# nanoRF.net
KiCad netlist of a schematic drawn in EAGLE
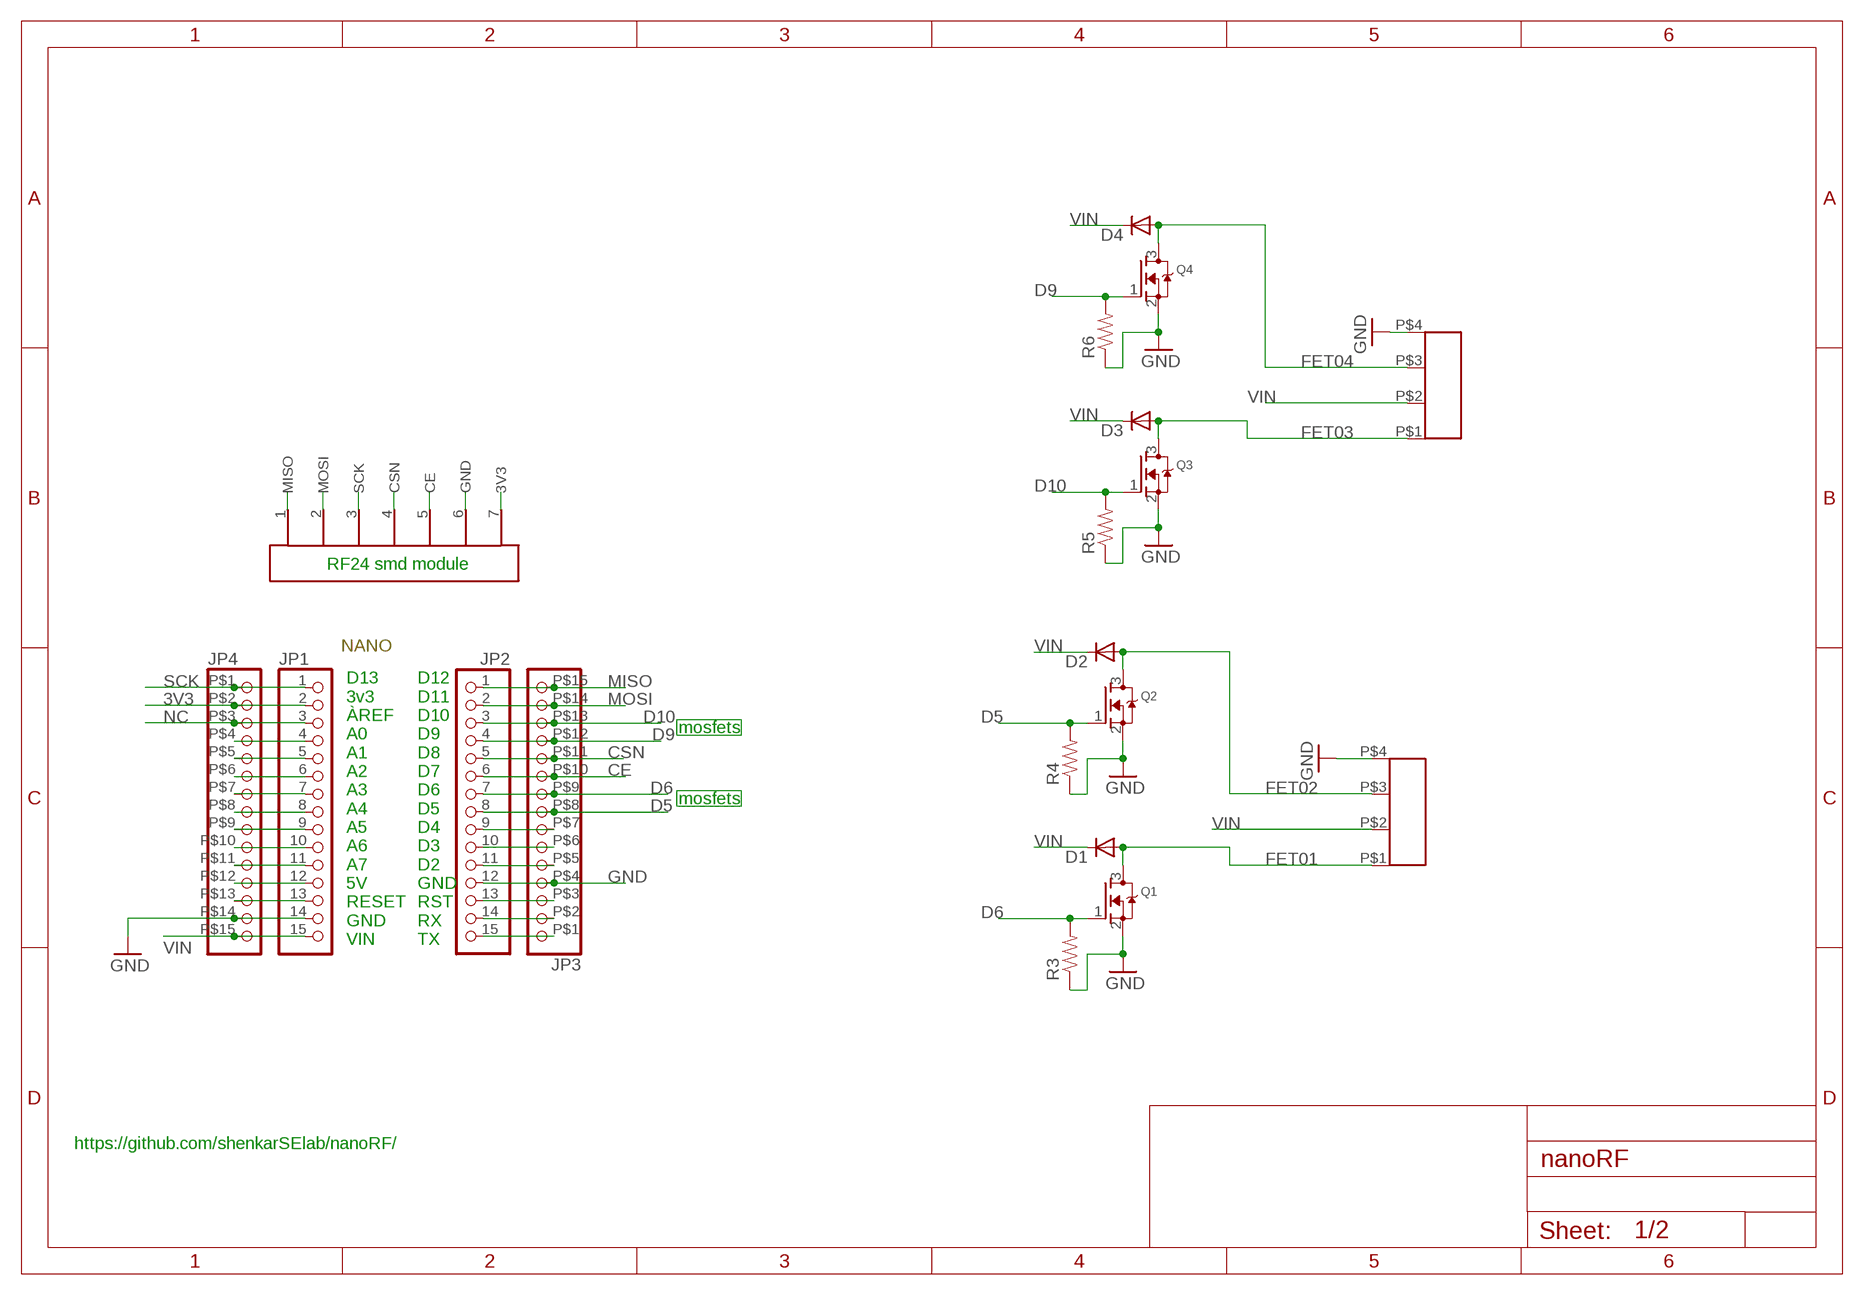
[diagram p0: schematic, sheet 1]

(export (version "E")
  (design (tool "Eeschema 10.0.6"))
  (components
    (comp (ref "D1")
      (value "DIODE-DO-214AC")
      (footprint "eagle-import:DO-214AC")
      (libsource (lib "eagle-import") (part "DIODE-DO-214AC"))
    )
    (comp (ref "D2")
      (value "DIODE-DO-214AC")
      (footprint "eagle-import:DO-214AC")
      (libsource (lib "eagle-import") (part "DIODE-DO-214AC"))
    )
    (comp (ref "D3")
      (value "DIODE-DO-214AC")
      (footprint "eagle-import:DO-214AC")
      (libsource (lib "eagle-import") (part "DIODE-DO-214AC"))
    )
    (comp (ref "D4")
      (value "DIODE-DO-214AC")
      (footprint "eagle-import:DO-214AC")
      (libsource (lib "eagle-import") (part "DIODE-DO-214AC"))
    )
    (comp (ref "JP1")
      (value "HEADER-1X15RND")
      (footprint "eagle-import:1X15_ROUND_70")
      (libsource (lib "eagle-import") (part "HEADER-1X15RND"))
    )
    (comp (ref "JP2")
      (value "HEADER-1X15RND")
      (footprint "eagle-import:1X15_ROUND_70")
      (libsource (lib "eagle-import") (part "HEADER-1X15RND"))
    )
    (comp (ref "JP3")
      (value "HEADER-1X15LONG")
      (footprint "eagle-import:1X15_LONG")
      (libsource (lib "eagle-import") (part "HEADER-1X15LONG"))
    )
    (comp (ref "JP4")
      (value "HEADER-1X15LONG")
      (footprint "eagle-import:1X15_LONG")
      (libsource (lib "eagle-import") (part "HEADER-1X15LONG"))
    )
    (comp (ref "MOSFET-12")
      (value "FATPAD4LONG")
      (footprint "eagle-import:FATFAD4-LONG")
      (libsource (lib "eagle-import") (part "FATPAD4LONG"))
    )
    (comp (ref "MOSFET-34")
      (value "FATPAD4LONG")
      (footprint "eagle-import:FATFAD4-LONG")
      (libsource (lib "eagle-import") (part "FATPAD4LONG"))
    )
    (comp (ref "Q1")
      (value "MOSFET-NWAVE")
      (footprint "eagle-import:SOT23-W")
      (libsource (lib "eagle-import") (part "MOSFET-NWAVE"))
    )
    (comp (ref "Q2")
      (value "MOSFET-NWAVE")
      (footprint "eagle-import:SOT23-W")
      (libsource (lib "eagle-import") (part "MOSFET-NWAVE"))
    )
    (comp (ref "Q3")
      (value "MOSFET-NWAVE")
      (footprint "eagle-import:SOT23-W")
      (libsource (lib "eagle-import") (part "MOSFET-NWAVE"))
    )
    (comp (ref "Q4")
      (value "MOSFET-NWAVE")
      (footprint "eagle-import:SOT23-W")
      (libsource (lib "eagle-import") (part "MOSFET-NWAVE"))
    )
    (comp (ref "R3")
      (value "RESISTOR0805-RES")
      (footprint "eagle-import:0805")
      (libsource (lib "eagle-import") (part "RESISTOR0805-RES"))
    )
    (comp (ref "R4")
      (value "RESISTOR0805-RES")
      (footprint "eagle-import:0805")
      (libsource (lib "eagle-import") (part "RESISTOR0805-RES"))
    )
    (comp (ref "R5")
      (value "RESISTOR0805-RES")
      (footprint "eagle-import:0805")
      (libsource (lib "eagle-import") (part "RESISTOR0805-RES"))
    )
    (comp (ref "R6")
      (value "RESISTOR0805-RES")
      (footprint "eagle-import:0805")
      (libsource (lib "eagle-import") (part "RESISTOR0805-RES"))
    )
    (comp (ref "RF24")
      (value "1X7-SMDPADS")
      (footprint "eagle-import:SMD1,27-2,54")
      (libsource (lib "eagle-import") (part "1X7-SMDPADS"))
    )
  )
  (nets
    (net (code "1") (name "3V3") (class "Default")
      (node (ref "JP1") (pin "2") (pinfunction "2_2") (pintype "passive"))
      (node (ref "JP4") (pin "P$2") (pinfunction "2_P$2") (pintype "passive"))
      (node (ref "RF24") (pin "7") (pinfunction "3V3_7") (pintype "bidirectional"))
    )
    (net (code "2") (name "CE") (class "Default")
      (node (ref "JP2") (pin "6") (pinfunction "6_6") (pintype "passive"))
      (node (ref "JP3") (pin "P$10") (pinfunction "10_P$10") (pintype "passive"))
      (node (ref "RF24") (pin "5") (pinfunction "CE_5") (pintype "bidirectional"))
    )
    (net (code "3") (name "CSN") (class "Default")
      (node (ref "JP2") (pin "5") (pinfunction "5_5") (pintype "passive"))
      (node (ref "JP3") (pin "P$11") (pinfunction "11_P$11") (pintype "passive"))
      (node (ref "RF24") (pin "4") (pinfunction "CSN_4") (pintype "bidirectional"))
    )
    (net (code "4") (name "D5") (class "Default")
      (node (ref "JP2") (pin "8") (pinfunction "8_8") (pintype "passive"))
      (node (ref "JP3") (pin "P$8") (pinfunction "8_P$8") (pintype "passive"))
      (node (ref "Q2") (pin "1") (pinfunction "G_1") (pintype "bidirectional"))
      (node (ref "R4") (pin "2") (pinfunction "2_2") (pintype "passive"))
    )
    (net (code "5") (name "D6") (class "Default")
      (node (ref "JP2") (pin "7") (pinfunction "7_7") (pintype "passive"))
      (node (ref "JP3") (pin "P$9") (pinfunction "9_P$9") (pintype "passive"))
      (node (ref "Q1") (pin "1") (pinfunction "G_1") (pintype "bidirectional"))
      (node (ref "R3") (pin "2") (pinfunction "2_2") (pintype "passive"))
    )
    (net (code "6") (name "D9") (class "Default")
      (node (ref "JP2") (pin "4") (pinfunction "4_4") (pintype "passive"))
      (node (ref "JP3") (pin "P$12") (pinfunction "12_P$12") (pintype "passive"))
      (node (ref "Q4") (pin "1") (pinfunction "G_1") (pintype "bidirectional"))
      (node (ref "R6") (pin "2") (pinfunction "2_2") (pintype "passive"))
    )
    (net (code "7") (name "D10") (class "Default")
      (node (ref "JP2") (pin "3") (pinfunction "3_3") (pintype "passive"))
      (node (ref "JP3") (pin "P$13") (pinfunction "13_P$13") (pintype "passive"))
      (node (ref "Q3") (pin "1") (pinfunction "G_1") (pintype "bidirectional"))
      (node (ref "R5") (pin "2") (pinfunction "2_2") (pintype "passive"))
    )
    (net (code "8") (name "FET01") (class "Default")
      (node (ref "D1") (pin "2") (pinfunction "A_2") (pintype "passive"))
      (node (ref "MOSFET-12") (pin "P$1") (pinfunction "P$1_P$1") (pintype "bidirectional"))
      (node (ref "Q1") (pin "3") (pinfunction "D_3") (pintype "bidirectional"))
    )
    (net (code "9") (name "FET02") (class "Default")
      (node (ref "D2") (pin "2") (pinfunction "A_2") (pintype "passive"))
      (node (ref "MOSFET-12") (pin "P$3") (pinfunction "P$3_P$3") (pintype "bidirectional"))
      (node (ref "Q2") (pin "3") (pinfunction "D_3") (pintype "bidirectional"))
    )
    (net (code "10") (name "FET03") (class "Default")
      (node (ref "D3") (pin "2") (pinfunction "A_2") (pintype "passive"))
      (node (ref "MOSFET-34") (pin "P$1") (pinfunction "P$1_P$1") (pintype "bidirectional"))
      (node (ref "Q3") (pin "3") (pinfunction "D_3") (pintype "bidirectional"))
    )
    (net (code "11") (name "FET04") (class "Default")
      (node (ref "D4") (pin "2") (pinfunction "A_2") (pintype "passive"))
      (node (ref "MOSFET-34") (pin "P$3") (pinfunction "P$3_P$3") (pintype "bidirectional"))
      (node (ref "Q4") (pin "3") (pinfunction "D_3") (pintype "bidirectional"))
    )
    (net (code "12") (name "GND") (class "Default")
      (node (ref "JP1") (pin "14") (pinfunction "14_14") (pintype "passive"))
      (node (ref "JP2") (pin "12") (pinfunction "12_12") (pintype "passive"))
      (node (ref "JP3") (pin "P$4") (pinfunction "4_P$4") (pintype "passive"))
      (node (ref "JP4") (pin "P$14") (pinfunction "14_P$14") (pintype "passive"))
      (node (ref "MOSFET-12") (pin "P$4") (pinfunction "P$4_P$4") (pintype "bidirectional"))
      (node (ref "MOSFET-34") (pin "P$4") (pinfunction "P$4_P$4") (pintype "bidirectional"))
      (node (ref "Q1") (pin "2") (pinfunction "S_2") (pintype "bidirectional"))
      (node (ref "Q2") (pin "2") (pinfunction "S_2") (pintype "bidirectional"))
      (node (ref "Q3") (pin "2") (pinfunction "S_2") (pintype "bidirectional"))
      (node (ref "Q4") (pin "2") (pinfunction "S_2") (pintype "bidirectional"))
      (node (ref "R3") (pin "1") (pinfunction "1_1") (pintype "passive"))
      (node (ref "R4") (pin "1") (pinfunction "1_1") (pintype "passive"))
      (node (ref "R5") (pin "1") (pinfunction "1_1") (pintype "passive"))
      (node (ref "R6") (pin "1") (pinfunction "1_1") (pintype "passive"))
      (node (ref "RF24") (pin "6") (pinfunction "GND_6") (pintype "bidirectional"))
    )
    (net (code "13") (name "MISO") (class "Default")
      (node (ref "JP2") (pin "1") (pinfunction "1_1") (pintype "passive"))
      (node (ref "JP3") (pin "P$15") (pinfunction "15_P$15") (pintype "passive"))
      (node (ref "RF24") (pin "1") (pinfunction "MISO_1") (pintype "bidirectional"))
    )
    (net (code "14") (name "MOSI") (class "Default")
      (node (ref "JP2") (pin "2") (pinfunction "2_2") (pintype "passive"))
      (node (ref "JP3") (pin "P$14") (pinfunction "14_P$14") (pintype "passive"))
      (node (ref "RF24") (pin "2") (pinfunction "MOSI_2") (pintype "bidirectional"))
    )
    (net (code "15") (name "NC") (class "Default")
      (node (ref "JP1") (pin "3") (pinfunction "3_3") (pintype "passive"))
      (node (ref "JP4") (pin "P$3") (pinfunction "3_P$3") (pintype "passive"))
    )
    (net (code "16") (name "Net-(JP3-1)") (class "Default")
      (node (ref "JP2") (pin "15") (pinfunction "15_15") (pintype "passive"))
      (node (ref "JP3") (pin "P$1") (pinfunction "1_P$1") (pintype "passive"))
    )
    (net (code "17") (name "Net-(JP3-2)") (class "Default")
      (node (ref "JP2") (pin "14") (pinfunction "14_14") (pintype "passive"))
      (node (ref "JP3") (pin "P$2") (pinfunction "2_P$2") (pintype "passive"))
    )
    (net (code "18") (name "Net-(JP3-3)") (class "Default")
      (node (ref "JP2") (pin "13") (pinfunction "13_13") (pintype "passive"))
      (node (ref "JP3") (pin "P$3") (pinfunction "3_P$3") (pintype "passive"))
    )
    (net (code "19") (name "Net-(JP3-5)") (class "Default")
      (node (ref "JP2") (pin "11") (pinfunction "11_11") (pintype "passive"))
      (node (ref "JP3") (pin "P$5") (pinfunction "5_P$5") (pintype "passive"))
    )
    (net (code "20") (name "Net-(JP3-6)") (class "Default")
      (node (ref "JP2") (pin "10") (pinfunction "10_10") (pintype "passive"))
      (node (ref "JP3") (pin "P$6") (pinfunction "6_P$6") (pintype "passive"))
    )
    (net (code "21") (name "Net-(JP3-7)") (class "Default")
      (node (ref "JP2") (pin "9") (pinfunction "9_9") (pintype "passive"))
      (node (ref "JP3") (pin "P$7") (pinfunction "7_P$7") (pintype "passive"))
    )
    (net (code "22") (name "Net-(JP4-4)") (class "Default")
      (node (ref "JP1") (pin "4") (pinfunction "4_4") (pintype "passive"))
      (node (ref "JP4") (pin "P$4") (pinfunction "4_P$4") (pintype "passive"))
    )
    (net (code "23") (name "Net-(JP4-5)") (class "Default")
      (node (ref "JP1") (pin "5") (pinfunction "5_5") (pintype "passive"))
      (node (ref "JP4") (pin "P$5") (pinfunction "5_P$5") (pintype "passive"))
    )
    (net (code "24") (name "Net-(JP4-6)") (class "Default")
      (node (ref "JP1") (pin "6") (pinfunction "6_6") (pintype "passive"))
      (node (ref "JP4") (pin "P$6") (pinfunction "6_P$6") (pintype "passive"))
    )
    (net (code "25") (name "Net-(JP4-7)") (class "Default")
      (node (ref "JP1") (pin "7") (pinfunction "7_7") (pintype "passive"))
      (node (ref "JP4") (pin "P$7") (pinfunction "7_P$7") (pintype "passive"))
    )
    (net (code "26") (name "Net-(JP4-8)") (class "Default")
      (node (ref "JP1") (pin "8") (pinfunction "8_8") (pintype "passive"))
      (node (ref "JP4") (pin "P$8") (pinfunction "8_P$8") (pintype "passive"))
    )
    (net (code "27") (name "Net-(JP4-9)") (class "Default")
      (node (ref "JP1") (pin "9") (pinfunction "9_9") (pintype "passive"))
      (node (ref "JP4") (pin "P$9") (pinfunction "9_P$9") (pintype "passive"))
    )
    (net (code "28") (name "Net-(JP4-10)") (class "Default")
      (node (ref "JP1") (pin "10") (pinfunction "10_10") (pintype "passive"))
      (node (ref "JP4") (pin "P$10") (pinfunction "10_P$10") (pintype "passive"))
    )
    (net (code "29") (name "Net-(JP4-11)") (class "Default")
      (node (ref "JP1") (pin "11") (pinfunction "11_11") (pintype "passive"))
      (node (ref "JP4") (pin "P$11") (pinfunction "11_P$11") (pintype "passive"))
    )
    (net (code "30") (name "Net-(JP4-12)") (class "Default")
      (node (ref "JP1") (pin "12") (pinfunction "12_12") (pintype "passive"))
      (node (ref "JP4") (pin "P$12") (pinfunction "12_P$12") (pintype "passive"))
    )
    (net (code "31") (name "Net-(JP4-13)") (class "Default")
      (node (ref "JP1") (pin "13") (pinfunction "13_13") (pintype "passive"))
      (node (ref "JP4") (pin "P$13") (pinfunction "13_P$13") (pintype "passive"))
    )
    (net (code "32") (name "SCK") (class "Default")
      (node (ref "JP1") (pin "1") (pinfunction "1_1") (pintype "passive"))
      (node (ref "JP4") (pin "P$1") (pinfunction "1_P$1") (pintype "passive"))
      (node (ref "RF24") (pin "3") (pinfunction "SCK_3") (pintype "bidirectional"))
    )
    (net (code "33") (name "VIN") (class "Default")
      (node (ref "D1") (pin "1") (pinfunction "C_1") (pintype "passive"))
      (node (ref "D2") (pin "1") (pinfunction "C_1") (pintype "passive"))
      (node (ref "D3") (pin "1") (pinfunction "C_1") (pintype "passive"))
      (node (ref "D4") (pin "1") (pinfunction "C_1") (pintype "passive"))
      (node (ref "JP1") (pin "15") (pinfunction "15_15") (pintype "passive"))
      (node (ref "JP4") (pin "P$15") (pinfunction "15_P$15") (pintype "passive"))
      (node (ref "MOSFET-12") (pin "P$2") (pinfunction "P$2_P$2") (pintype "bidirectional"))
      (node (ref "MOSFET-34") (pin "P$2") (pinfunction "P$2_P$2") (pintype "bidirectional"))
    )
  )
)
